# PedalMain.net
KiCad netlist of a schematic drawn in Altium Designer
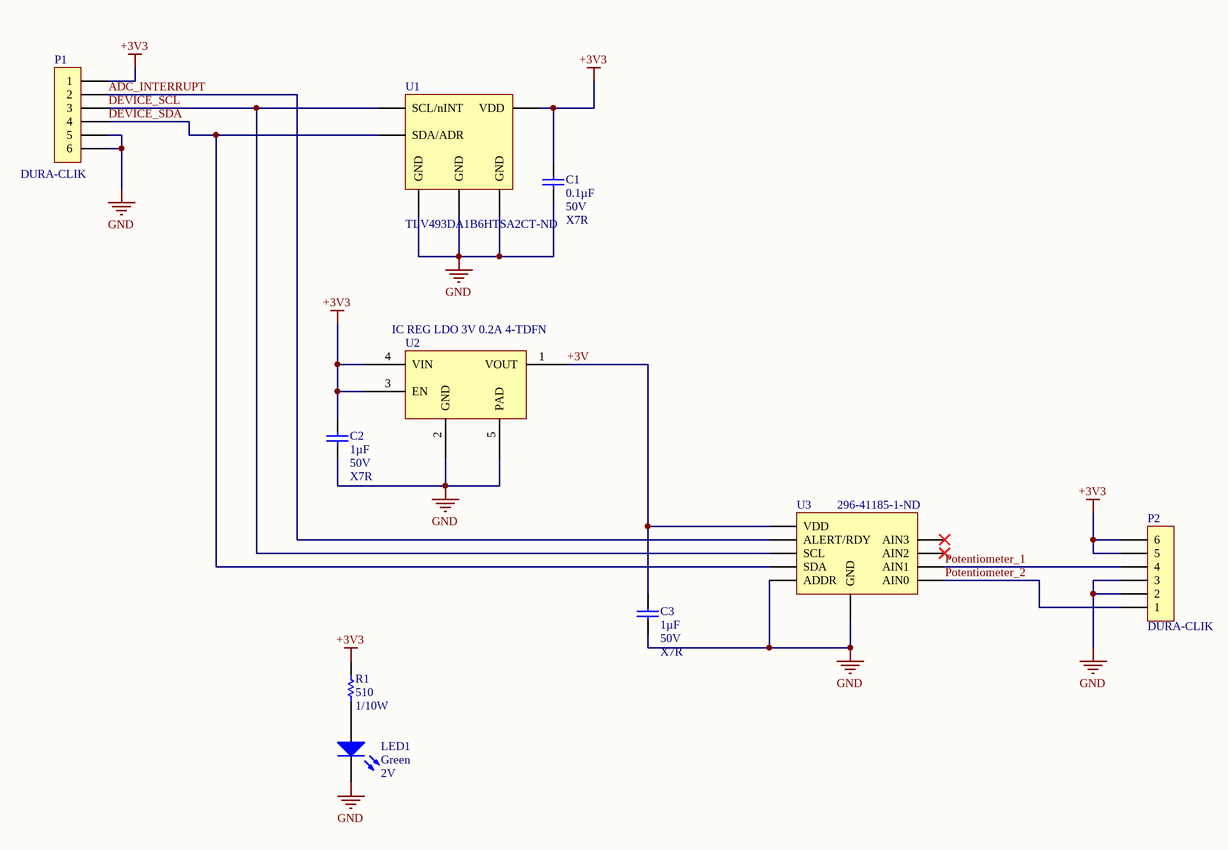
[diagram p0: PedalMain.SchDoc]

(export (version "E")
  (design (tool "Eeschema 10.0.6"))
  (components
    (comp (ref "C1")
      (value "CAP CER 0.1UF 50V 10% X7R 0603")
      (footprint "CAP, 0603")
      (description "0.10µF ±10% 50V Ceramic Capacitor X7R 0603 (1608 Metric)")
      (fields
        (field (name "TOLERANCE") "±10%")
        (field (name "CAPACITANCE") "0.1µF")
        (field (name "VOLTAGE") "50V")
        (field (name "TEMPERATURE COEFFICIENT") "X7R")
      )
      (libsource (lib "Schematic Diagrams") (part "CAP CER 0.1UF 50V 10% X7R 0603"))
    )
    (comp (ref "C2")
      (value "CAP CER 1UF 50V 10% X7R 0603")
      (footprint "CAP, 0603")
      (description "1µF ±10% 50V Ceramic Capacitor X7R 0603 (1608 Metric)")
      (fields
        (field (name "TOLERANCE") "±10%")
        (field (name "CAPACITANCE") "1µF")
        (field (name "VOLTAGE") "50V")
        (field (name "TEMPERATURE COEFFICIENT") "X7R")
      )
      (libsource (lib "Schematic Diagrams") (part "CAP CER 1UF 50V 10% X7R 0603"))
    )
    (comp (ref "C3")
      (value "CAP CER 1UF 50V 10% X7R 0603")
      (footprint "CAP, 0603")
      (description "1µF ±10% 50V Ceramic Capacitor X7R 0603 (1608 Metric)")
      (fields
        (field (name "TOLERANCE") "±10%")
        (field (name "CAPACITANCE") "1µF")
        (field (name "VOLTAGE") "50V")
        (field (name "TEMPERATURE COEFFICIENT") "X7R")
      )
      (libsource (lib "Schematic Diagrams") (part "CAP CER 1UF 50V 10% X7R 0603"))
    )
    (comp (ref "LED1")
      (value "LED GREEN CLEAR 2V 0603")
      (footprint "LED_0603")
      (description "Green 572nm LED Indication - Discrete 2V 0603 (1608 Metric)")
      (fields
        (field (name "MANUFACTURER") "Wurth Electronics Inc.")
        (field (name "MANUFACTURER PART NUMBER") "150060VS75000")
        (field (name "COLOR") "Green")
        (field (name "VOLTAGE - FORWARD (VF) (TYP)") "2V")
      )
      (libsource (lib "Schematic Diagrams") (part "LED GREEN CLEAR 2V 0603"))
    )
    (comp (ref "P1")
      (value "DURA-CLIK")
      (footprint "CONN, 6POS DURA-CLIK VERT")
      (description "6 Positions Header, Shrouded Connector 0.079\" (2.00mm) Surface Mount, Vertical Tin")
      (fields (field (name "MANUFACTURER") "Molex") (field (name "MANUFACTURER PART NUMBER") "5600200820"))
      (libsource (lib "") (part "CONN 6POS DURA-CLIK 0.079{dblquote}_1"))
    )
    (comp (ref "P2")
      (value "DURA-CLIK")
      (footprint "CONN, 6POS DURA-CLIK VERT")
      (description "6 Positions Header, Shrouded Connector 0.079\" (2.00mm) Surface Mount, Vertical Tin")
      (fields (field (name "MANUFACTURER") "Molex") (field (name "MANUFACTURER PART NUMBER") "5600200820"))
      (libsource (lib "Schematic Diagrams") (part "CONN 6POS DURA-CLIK 0.079{dblquote}"))
    )
    (comp (ref "R1")
      (value "RES 510 OHM 5% 1/10W 0603")
      (footprint "RES, 0603")
      (description "RES SMD 510 OHM 5% 1/10W 0603")
      (fields
        (field (name "TOLERANCE") "±5%")
        (field (name "RESISTANCE") "510")
        (field (name "POWER") "1/10W")
      )
      (libsource (lib "Schematic Diagrams") (part "RES 510 OHM 5% 1/10W 0603"))
    )
    (comp (ref "U1")
      (value "HALL EFFECT")
      (footprint "IC TLV496D MAG SENSOR TSOP-6")
      (description "Hall Effect Sensor Linear, Rotary Position External Magnet Not Included SMD (SMT) Tab")
      (fields
        (field (name "MANUFACTURER") "Infineon Technologies")
        (field (name "MANUFACTURER PART NUMBER") "TLV493DA1B6HTSA2")
        (field (name "SUPPLIER PART NUMBER 1") "TLV493DA1B6HTSA2CT-ND")
      )
      (libsource (lib "Schematic Diagrams") (part "IC SENSOR HALL I2C TSOP-6"))
    )
    (comp (ref "U2")
      (value "IC REG LDO 3V 0.2A 4-TDFN")
      (footprint "IC REG LDO 3V 0.2A 4-TDFN")
      (fields
        (field (name "MANUFACTURER") "Microchip Technology")
        (field (name "MANUFACTURER PART NUMBER") "MIC94310-PYMT-TR")
      )
      (libsource (lib "Schematic Diagrams") (part "IC REG LDO 3V 0.2A 4-TDFN"))
    )
    (comp (ref "U3")
      (value "Quad ADC")
      (footprint "IC ADC VSSOP10")
      (description "12 Bit Analog to Digital Converter 4 Input 1 Sigma-Delta 10-VSSOP")
      (fields
        (field (name "MANUFACTURER") "Texas Instruments")
        (field (name "MANUFACTURER PART NUMBER") "ADS1015IDGSR")
        (field (name "SUPPLIER PART NUMBER 1") "296-41185-1-ND")
      )
      (libsource (lib "Schematic Diagrams") (part "IC ADC 12-BIT VSSOP-10"))
    )
  )
  (nets
    (net (code "1") (name "+3V3") (class "Default")
      (node (ref "C1") (pin "1") (pinfunction "1_1") (pintype "passive"))
      (node (ref "C2") (pin "1") (pinfunction "1_1") (pintype "passive"))
      (node (ref "P1") (pin "1") (pinfunction "1_1") (pintype "passive"))
      (node (ref "P2") (pin "5") (pinfunction "5_5") (pintype "passive"))
      (node (ref "P2") (pin "6") (pinfunction "6_6") (pintype "passive"))
      (node (ref "R1") (pin "1") (pinfunction "1_1") (pintype "passive"))
      (node (ref "U1") (pin "4") (pinfunction "VDD_4") (pintype "passive"))
      (node (ref "U2") (pin "3") (pinfunction "EN_3") (pintype "passive"))
      (node (ref "U2") (pin "4") (pinfunction "VIN_4") (pintype "passive"))
    )
    (net (code "2") (name "/+3V") (class "Default")
      (node (ref "C3") (pin "1") (pinfunction "1_1") (pintype "passive"))
      (node (ref "U2") (pin "1") (pinfunction "VOUT_1") (pintype "passive"))
      (node (ref "U3") (pin "8") (pinfunction "VDD_8") (pintype "passive"))
    )
    (net (code "3") (name "/ADC_INTERRUPT") (class "Default")
      (node (ref "P1") (pin "2") (pinfunction "2_2") (pintype "passive"))
      (node (ref "U3") (pin "2") (pinfunction "ALERT/RDY_2") (pintype "passive"))
    )
    (net (code "4") (name "/DEVICE_SCL") (class "Default")
      (node (ref "P1") (pin "3") (pinfunction "3_3") (pintype "passive"))
      (node (ref "U1") (pin "1") (pinfunction "SCL/nINT_1") (pintype "passive"))
      (node (ref "U3") (pin "10") (pinfunction "SCL_10") (pintype "passive"))
    )
    (net (code "5") (name "/DEVICE_SDA") (class "Default")
      (node (ref "P1") (pin "4") (pinfunction "4_4") (pintype "passive"))
      (node (ref "U1") (pin "6") (pinfunction "SDA/ADR_6") (pintype "passive"))
      (node (ref "U3") (pin "9") (pinfunction "SDA_9") (pintype "passive"))
    )
    (net (code "6") (name "/Potentiometer_1") (class "Default")
      (node (ref "P2") (pin "4") (pinfunction "4_4") (pintype "passive"))
      (node (ref "U3") (pin "5") (pinfunction "AIN1_5") (pintype "passive"))
    )
    (net (code "7") (name "/Potentiometer_2") (class "Default")
      (node (ref "P2") (pin "1") (pinfunction "1_1") (pintype "passive"))
      (node (ref "U3") (pin "4") (pinfunction "AIN0_4") (pintype "passive"))
    )
    (net (code "8") (name "GND") (class "Default")
      (node (ref "C1") (pin "2") (pinfunction "2_2") (pintype "passive"))
      (node (ref "C2") (pin "2") (pinfunction "2_2") (pintype "passive"))
      (node (ref "C3") (pin "2") (pinfunction "2_2") (pintype "passive"))
      (node (ref "LED1") (pin "2") (pinfunction "K_2") (pintype "passive"))
      (node (ref "P1") (pin "5") (pinfunction "5_5") (pintype "passive"))
      (node (ref "P1") (pin "6") (pinfunction "6_6") (pintype "passive"))
      (node (ref "P2") (pin "2") (pinfunction "2_2") (pintype "passive"))
      (node (ref "P2") (pin "3") (pinfunction "3_3") (pintype "passive"))
      (node (ref "U1") (pin "2") (pinfunction "GND_2") (pintype "passive"))
      (node (ref "U1") (pin "3") (pinfunction "GND_3") (pintype "passive"))
      (node (ref "U1") (pin "5") (pinfunction "GND_5") (pintype "passive"))
      (node (ref "U2") (pin "2") (pinfunction "GND_2") (pintype "passive"))
      (node (ref "U2") (pin "5") (pinfunction "PAD_5") (pintype "passive"))
      (node (ref "U3") (pin "1") (pinfunction "ADDR_1") (pintype "passive"))
      (node (ref "U3") (pin "3") (pinfunction "GND_3") (pintype "passive"))
    )
    (net (code "9") (name "Net-(LED1-A)") (class "Default")
      (node (ref "LED1") (pin "1") (pinfunction "A_1") (pintype "passive"))
      (node (ref "R1") (pin "2") (pinfunction "2_2") (pintype "passive"))
    )
    (net (code "10") (name "unconnected-(U3-AIN2-Pad6)") (class "Default")
      (node (ref "U3") (pin "6") (pinfunction "AIN2_6") (pintype "passive+no_connect"))
    )
    (net (code "11") (name "unconnected-(U3-AIN3-Pad7)") (class "Default")
      (node (ref "U3") (pin "7") (pinfunction "AIN3_7") (pintype "passive+no_connect"))
    )
  )
)
